# NinjaPCR-140720.net
KiCad netlist of a schematic drawn in EAGLE
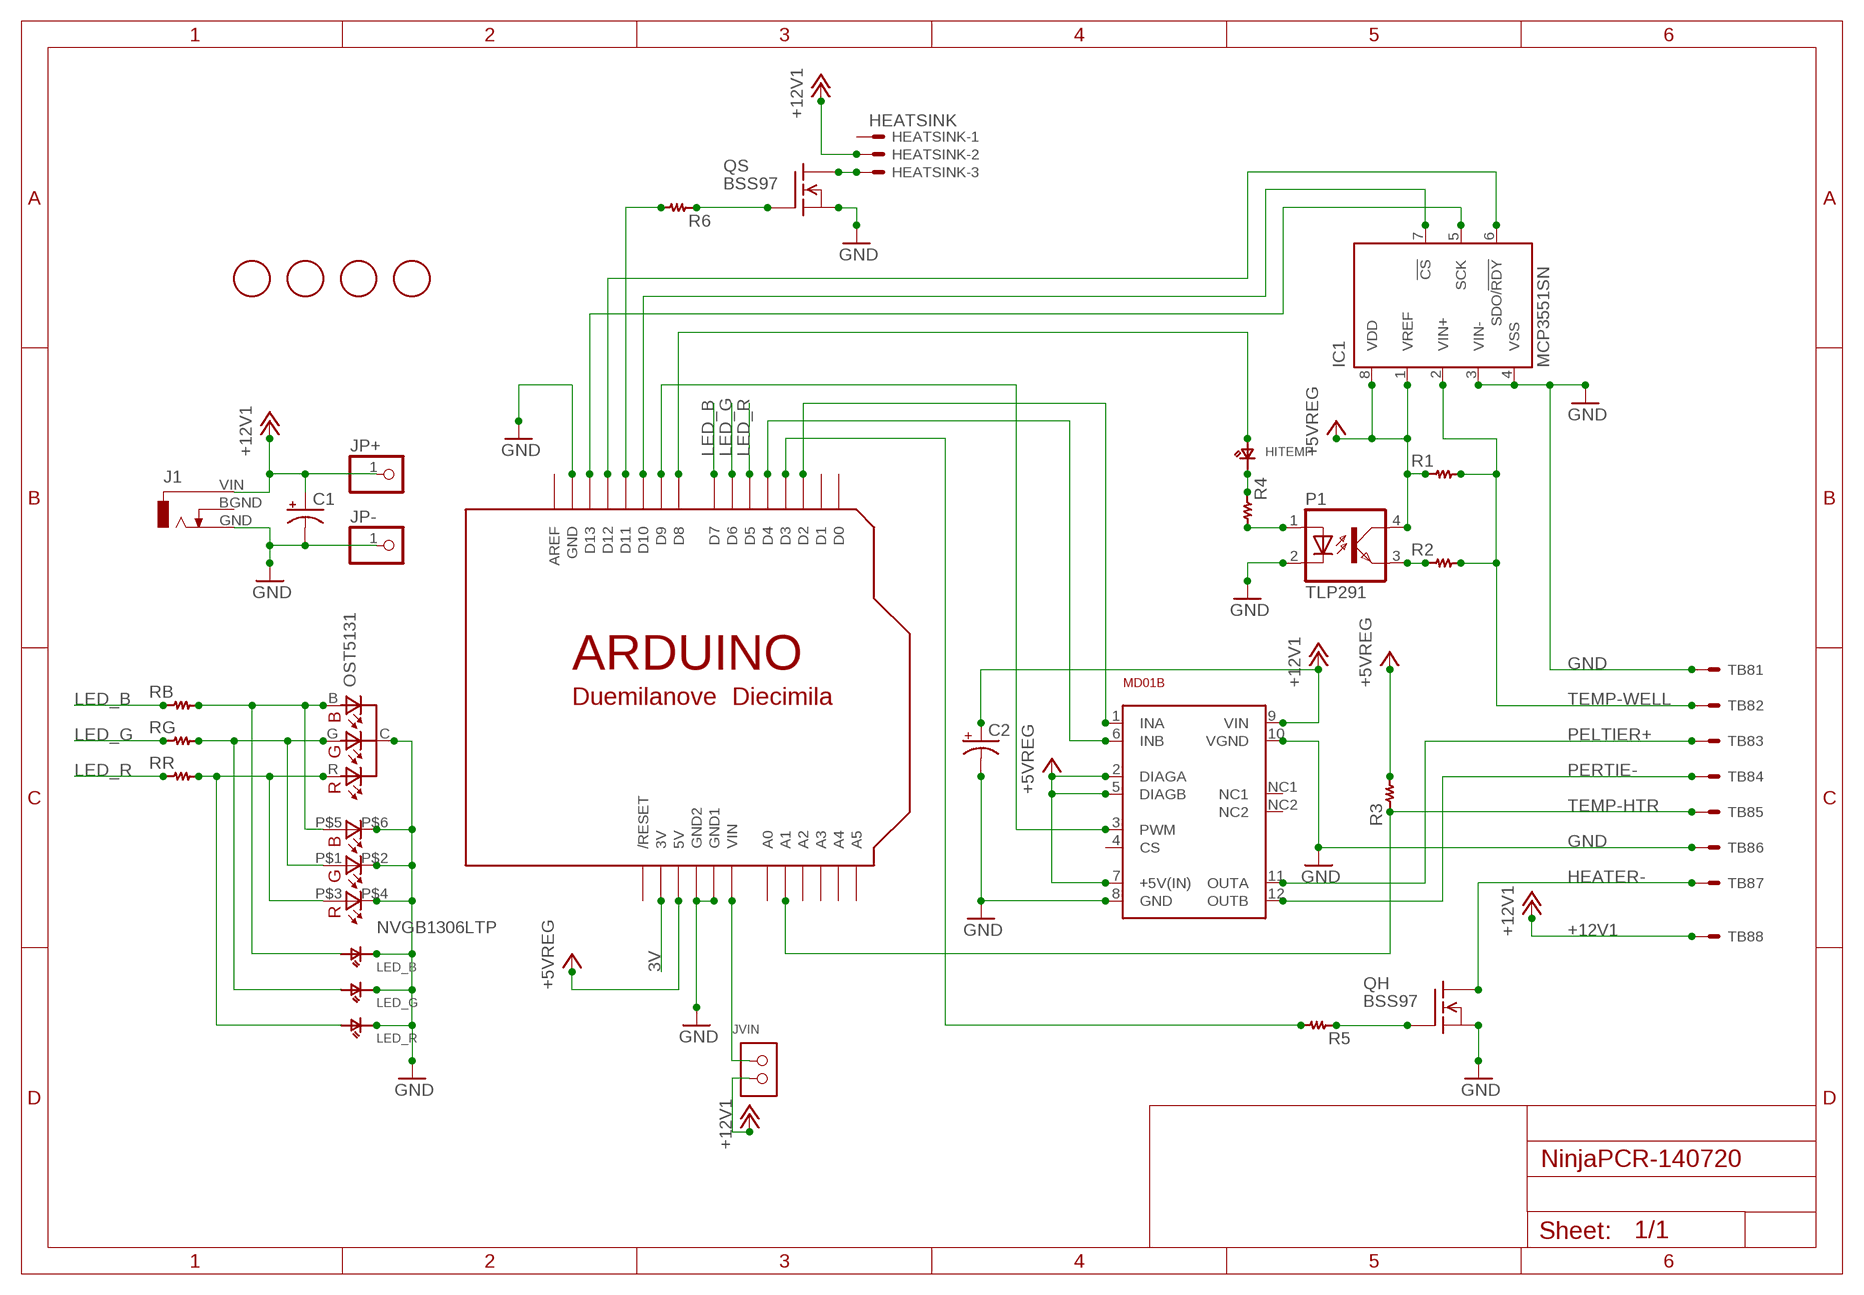
[diagram p0: schematic, sheet 1]

(export (version "E")
  (design (tool "Eeschema 10.0.6"))
  (components
    (comp (ref "C1")
      (value "CPOL-USE5-8.5")
      (footprint "eagle-import:E5-8,5")
      (libsource (lib "eagle-import") (part "CPOL-USE5-8.5"))
    )
    (comp (ref "C2")
      (value "CPOL-USE5-13")
      (footprint "eagle-import:E5-13")
      (libsource (lib "eagle-import") (part "CPOL-USE5-13"))
    )
    (comp (ref "HEATSINK")
      (value "HEATSINK")
      (footprint "eagle-import:22-23-2031")
      (fields (field (name "MF") "MOLEX") (field (name "MPN") "22-23-2031"))
      (libsource (lib "eagle-import") (part "22-23-2031"))
    )
    (comp (ref "HITEMP")
      (value "LED1608")
      (footprint "eagle-import:SMD_1608_0603")
      (libsource (lib "eagle-import") (part "LED1608"))
    )
    (comp (ref "IC1")
      (value "MCP3551SN")
      (footprint "eagle-import:SO-08")
      (fields (field (name "MPN") "MCP3551-E/SN"))
      (libsource (lib "eagle-import") (part "MCP355SN1"))
    )
    (comp (ref "J1")
      (value "DCJ0303")
      (footprint "eagle-import:DCJ0303")
      (libsource (lib "eagle-import") (part "DCJ0303"))
    )
    (comp (ref "JP+")
      (value "PINHD-1X1")
      (footprint "eagle-import:1X01")
      (libsource (lib "eagle-import") (part "PINHD-1X1"))
    )
    (comp (ref "JP-")
      (value "PINHD-1X1")
      (footprint "eagle-import:1X01")
      (libsource (lib "eagle-import") (part "PINHD-1X1"))
    )
    (comp (ref "JVIN")
      (value "1X02")
      (footprint "eagle-import:1X02_1.1_UNSIGNED")
      (libsource (lib "eagle-import") (part "1X02"))
    )
    (comp (ref "LED_B")
      (value "LED2012")
      (footprint "eagle-import:SMD_2012_0805")
      (libsource (lib "eagle-import") (part "LED2012"))
    )
    (comp (ref "LED_G")
      (value "LED2012")
      (footprint "eagle-import:SMD_2012_0805")
      (libsource (lib "eagle-import") (part "LED2012"))
    )
    (comp (ref "LED_R")
      (value "LED2012")
      (footprint "eagle-import:SMD_2012_0805")
      (libsource (lib "eagle-import") (part "LED2012"))
    )
    (comp (ref "MD01B")
      (value "VNH3SP30+4PINN")
      (footprint "eagle-import:VNH3SP30+4PIN_NOHOLES")
      (libsource (lib "eagle-import") (part "VNH3SP30+4PINN"))
    )
    (comp (ref "P1")
      (value "TLP291")
      (footprint "eagle-import:MINI-FLAT-4")
      (libsource (lib "eagle-import") (part "TLP283"))
    )
    (comp (ref "QH")
      (value "BSS97")
      (footprint "eagle-import:TO202")
      (libsource (lib "eagle-import") (part "BSS97"))
    )
    (comp (ref "QS")
      (value "BSS97")
      (footprint "eagle-import:TO202")
      (libsource (lib "eagle-import") (part "BSS97"))
    )
    (comp (ref "R1")
      (value "R_SMD1608")
      (footprint "eagle-import:SMD_1608_0603")
      (libsource (lib "eagle-import") (part "R_SMD1608"))
    )
    (comp (ref "R2")
      (value "R_SMD1608")
      (footprint "eagle-import:SMD_1608_0603")
      (libsource (lib "eagle-import") (part "R_SMD1608"))
    )
    (comp (ref "R3")
      (value "R_SMD1608")
      (footprint "eagle-import:SMD_1608_0603")
      (libsource (lib "eagle-import") (part "R_SMD1608"))
    )
    (comp (ref "R4")
      (value "R_SMD1608")
      (footprint "eagle-import:SMD_1608_0603")
      (libsource (lib "eagle-import") (part "R_SMD1608"))
    )
    (comp (ref "R5")
      (value "R_SMD1608")
      (footprint "eagle-import:SMD_1608_0603")
      (libsource (lib "eagle-import") (part "R_SMD1608"))
    )
    (comp (ref "R6")
      (value "R_SMD1608")
      (footprint "eagle-import:SMD_1608_0603")
      (libsource (lib "eagle-import") (part "R_SMD1608"))
    )
    (comp (ref "RB")
      (value "R_SMD1608")
      (footprint "eagle-import:SMD_1608_0603")
      (libsource (lib "eagle-import") (part "R_SMD1608"))
    )
    (comp (ref "RG")
      (value "R_SMD1608")
      (footprint "eagle-import:SMD_1608_0603")
      (libsource (lib "eagle-import") (part "R_SMD1608"))
    )
    (comp (ref "RR")
      (value "R_SMD1608")
      (footprint "eagle-import:SMD_1608_0603")
      (libsource (lib "eagle-import") (part "R_SMD1608"))
    )
    (comp (ref "TB8")
      (value "TB112A-2-8")
      (footprint "eagle-import:TB112A-2-8")
      (libsource (lib "eagle-import") (part "TB112A-2-8"))
    )
    (comp (ref "U$1")
      (value "OST5131")
      (footprint "eagle-import:OSTA5131")
      (libsource (lib "eagle-import") (part "OST5131"))
    )
    (comp (ref "U$2")
      (value "FIDUCIAL")
      (footprint "eagle-import:FIDUCIAL_1MM")
      (libsource (lib "eagle-import") (part "FIDUCIAL"))
    )
    (comp (ref "U$3")
      (value "ARDUINODUEMILANOVE")
      (footprint "eagle-import:ARDUINO")
      (libsource (lib "eagle-import") (part "ARDUINODUEMILANOVE"))
    )
    (comp (ref "U$4")
      (value "FIDUCIAL")
      (footprint "eagle-import:FIDUCIAL_1MM")
      (libsource (lib "eagle-import") (part "FIDUCIAL"))
    )
    (comp (ref "U$5")
      (value "FIDUCIAL")
      (footprint "eagle-import:FIDUCIAL_1MM")
      (libsource (lib "eagle-import") (part "FIDUCIAL"))
    )
    (comp (ref "U$6")
      (value "FIDUCIAL")
      (footprint "eagle-import:FIDUCIAL_1MM")
      (libsource (lib "eagle-import") (part "FIDUCIAL"))
    )
    (comp (ref "U$8")
      (value "NVGB1306LTP")
      (footprint "eagle-import:NVGB1306L_TINYPADS")
      (libsource (lib "eagle-import") (part "NVGB1306LTP"))
    )
  )
  (nets
    (net (code "1") (name "+5VREG") (class "Default")
      (node (ref "IC1") (pin "1") (pinfunction "VREF_1") (pintype "input"))
      (node (ref "IC1") (pin "8") (pinfunction "VDD_8") (pintype "power_in"))
      (node (ref "MD01B") (pin "2") (pinfunction "DIAGA_2") (pintype "passive"))
      (node (ref "MD01B") (pin "5") (pinfunction "DIAGB_5") (pintype "passive"))
      (node (ref "MD01B") (pin "7") (pinfunction "+5V(IN)_7") (pintype "power_in"))
      (node (ref "P1") (pin "4") (pinfunction "COL_4") (pintype "passive"))
      (node (ref "R1") (pin "P$1") (pinfunction "1_P$1") (pintype "bidirectional"))
      (node (ref "R3") (pin "P$2") (pinfunction "2_P$2") (pintype "bidirectional"))
      (node (ref "U$3") (pin "5V") (pinfunction "5V_5V") (pintype "power_in"))
    )
    (net (code "2") (name "+12V1") (class "Default")
      (node (ref "C1") (pin "+") (pinfunction "+_+") (pintype "passive"))
      (node (ref "C2") (pin "+") (pinfunction "+_+") (pintype "passive"))
      (node (ref "HEATSINK") (pin "2") (pinfunction "S_2") (pintype "passive"))
      (node (ref "J1") (pin "VIN") (pinfunction "VIN_VIN") (pintype "passive"))
      (node (ref "JP+") (pin "1") (pinfunction "1_1") (pintype "passive"))
      (node (ref "JVIN") (pin "2") (pinfunction "2_2") (pintype "passive"))
      (node (ref "MD01B") (pin "9") (pinfunction "VIN_9") (pintype "power_in"))
      (node (ref "TB8") (pin "P$8") (pinfunction "S_P$8") (pintype "passive"))
    )
    (net (code "3") (name "/3V") (class "Default")
      (node (ref "U$3") (pin "3V") (pinfunction "3V_3V") (pintype "power_in"))
    )
    (net (code "4") (name "/HEATER-") (class "Default")
      (node (ref "QH") (pin "2") (pinfunction "D_2") (pintype "passive"))
      (node (ref "TB8") (pin "P$7") (pinfunction "S_P$7") (pintype "passive"))
    )
    (net (code "5") (name "/LED_B") (class "Default")
      (node (ref "RB") (pin "P$1") (pinfunction "1_P$1") (pintype "bidirectional"))
      (node (ref "U$3") (pin "D7") (pinfunction "D7_D7") (pintype "bidirectional"))
    )
    (net (code "6") (name "/LED_G") (class "Default")
      (node (ref "RG") (pin "P$1") (pinfunction "1_P$1") (pintype "bidirectional"))
      (node (ref "U$3") (pin "D6") (pinfunction "D6_D6") (pintype "bidirectional"))
    )
    (net (code "7") (name "/LED_R") (class "Default")
      (node (ref "RR") (pin "P$1") (pinfunction "1_P$1") (pintype "bidirectional"))
      (node (ref "U$3") (pin "D5") (pinfunction "D5_D5") (pintype "bidirectional"))
    )
    (net (code "8") (name "/NC1") (class "Default")
      (node (ref "MD01B") (pin "NC1") (pinfunction "NC1_NC1") (pintype "power_in"))
    )
    (net (code "9") (name "/NC2") (class "Default")
      (node (ref "MD01B") (pin "NC2") (pinfunction "NC2_NC2") (pintype "power_in"))
    )
    (net (code "10") (name "/PELTIER+") (class "Default")
      (node (ref "MD01B") (pin "11") (pinfunction "OUTA_11") (pintype "passive"))
      (node (ref "TB8") (pin "P$3") (pinfunction "S_P$3") (pintype "passive"))
    )
    (net (code "11") (name "/PERTIE-") (class "Default")
      (node (ref "MD01B") (pin "12") (pinfunction "OUTB_12") (pintype "passive"))
      (node (ref "TB8") (pin "P$4") (pinfunction "S_P$4") (pintype "passive"))
    )
    (net (code "12") (name "/TEMP-HTR") (class "Default")
      (node (ref "R3") (pin "P$1") (pinfunction "1_P$1") (pintype "bidirectional"))
      (node (ref "TB8") (pin "P$5") (pinfunction "S_P$5") (pintype "passive"))
      (node (ref "U$3") (pin "A1") (pinfunction "A1_A1") (pintype "bidirectional"))
    )
    (net (code "13") (name "/TEMP-WELL") (class "Default")
      (node (ref "IC1") (pin "2") (pinfunction "VIN+_2") (pintype "input"))
      (node (ref "R1") (pin "P$2") (pinfunction "2_P$2") (pintype "bidirectional"))
      (node (ref "R2") (pin "P$2") (pinfunction "2_P$2") (pintype "bidirectional"))
      (node (ref "TB8") (pin "P$2") (pinfunction "S_P$2") (pintype "passive"))
    )
    (net (code "14") (name "GND") (class "Default")
      (node (ref "C1") (pin "-") (pinfunction "-_-") (pintype "passive"))
      (node (ref "C2") (pin "-") (pinfunction "-_-") (pintype "passive"))
      (node (ref "IC1") (pin "3") (pinfunction "VIN-_3") (pintype "input"))
      (node (ref "IC1") (pin "4") (pinfunction "VSS_4") (pintype "power_in"))
      (node (ref "J1") (pin "GND") (pinfunction "GND_GND") (pintype "passive"))
      (node (ref "JP-") (pin "1") (pinfunction "1_1") (pintype "passive"))
      (node (ref "LED_B") (pin "P$2") (pinfunction "C_P$2") (pintype "bidirectional"))
      (node (ref "LED_G") (pin "P$2") (pinfunction "C_P$2") (pintype "bidirectional"))
      (node (ref "LED_R") (pin "P$2") (pinfunction "C_P$2") (pintype "bidirectional"))
      (node (ref "MD01B") (pin "10") (pinfunction "VGND_10") (pintype "power_in"))
      (node (ref "MD01B") (pin "8") (pinfunction "GND_8") (pintype "power_in"))
      (node (ref "P1") (pin "2") (pinfunction "C_2") (pintype "passive"))
      (node (ref "QH") (pin "1") (pinfunction "S_1") (pintype "passive"))
      (node (ref "QS") (pin "1") (pinfunction "S_1") (pintype "passive"))
      (node (ref "TB8") (pin "P$1") (pinfunction "S_P$1") (pintype "passive"))
      (node (ref "TB8") (pin "P$6") (pinfunction "S_P$6") (pintype "passive"))
      (node (ref "U$1") (pin "C") (pinfunction "CC_C") (pintype "passive"))
      (node (ref "U$3") (pin "GND") (pinfunction "GND_GND") (pintype "power_in"))
      (node (ref "U$3") (pin "GND1") (pinfunction "GND1_GND1") (pintype "power_in"))
      (node (ref "U$3") (pin "GND2") (pinfunction "GND2_GND2") (pintype "power_in"))
      (node (ref "U$8") (pin "P$2") (pinfunction "GC_P$2") (pintype "passive"))
      (node (ref "U$8") (pin "P$4") (pinfunction "RC_P$4") (pintype "passive"))
      (node (ref "U$8") (pin "P$6") (pinfunction "BC_P$6") (pintype "passive"))
    )
    (net (code "15") (name "Net-(HEATSINKC-S)") (class "Default")
      (node (ref "HEATSINK") (pin "3") (pinfunction "S_3") (pintype "passive"))
      (node (ref "QS") (pin "2") (pinfunction "D_2") (pintype "passive"))
    )
    (net (code "16") (name "Net-(HITEMP-A)") (class "Default")
      (node (ref "HITEMP") (pin "P$1") (pinfunction "A_P$1") (pintype "bidirectional"))
      (node (ref "U$3") (pin "D8") (pinfunction "D8_D8") (pintype "bidirectional"))
    )
    (net (code "17") (name "Net-(HITEMP-C)") (class "Default")
      (node (ref "HITEMP") (pin "P$2") (pinfunction "C_P$2") (pintype "bidirectional"))
      (node (ref "R4") (pin "P$1") (pinfunction "1_P$1") (pintype "bidirectional"))
    )
    (net (code "18") (name "Net-(IC1-SCK)") (class "Default")
      (node (ref "IC1") (pin "5") (pinfunction "SCK_5") (pintype "input"))
      (node (ref "U$3") (pin "D13") (pinfunction "D13_D13") (pintype "bidirectional"))
    )
    (net (code "19") (name "Net-(IC1-SDO{slash}~{RDY})") (class "Default")
      (node (ref "IC1") (pin "6") (pinfunction "SDO/~{RDY}_6") (pintype "output"))
      (node (ref "U$3") (pin "D12") (pinfunction "D12_D12") (pintype "bidirectional"))
    )
    (net (code "20") (name "Net-(IC1-~{CS})") (class "Default")
      (node (ref "IC1") (pin "7") (pinfunction "~{CS}_7") (pintype "input"))
      (node (ref "U$3") (pin "D10") (pinfunction "D10_D10") (pintype "bidirectional"))
    )
    (net (code "21") (name "Net-(JVIN-Pad1)") (class "Default")
      (node (ref "JVIN") (pin "1") (pinfunction "1_1") (pintype "passive"))
      (node (ref "U$3") (pin "VIN") (pinfunction "VIN_VIN") (pintype "power_in"))
    )
    (net (code "22") (name "Net-(LED_B-A)") (class "Default")
      (node (ref "LED_B") (pin "P$1") (pinfunction "A_P$1") (pintype "bidirectional"))
      (node (ref "RB") (pin "P$2") (pinfunction "2_P$2") (pintype "bidirectional"))
      (node (ref "U$1") (pin "B") (pinfunction "BA_B") (pintype "passive"))
      (node (ref "U$8") (pin "P$5") (pinfunction "BA_P$5") (pintype "passive"))
    )
    (net (code "23") (name "Net-(LED_G-A)") (class "Default")
      (node (ref "LED_G") (pin "P$1") (pinfunction "A_P$1") (pintype "bidirectional"))
      (node (ref "RG") (pin "P$2") (pinfunction "2_P$2") (pintype "bidirectional"))
      (node (ref "U$1") (pin "G") (pinfunction "GA_G") (pintype "passive"))
      (node (ref "U$8") (pin "P$1") (pinfunction "GA_P$1") (pintype "passive"))
    )
    (net (code "24") (name "Net-(LED_R-A)") (class "Default")
      (node (ref "LED_R") (pin "P$1") (pinfunction "A_P$1") (pintype "bidirectional"))
      (node (ref "RR") (pin "P$2") (pinfunction "2_P$2") (pintype "bidirectional"))
      (node (ref "U$1") (pin "R") (pinfunction "RA_R") (pintype "passive"))
      (node (ref "U$8") (pin "P$3") (pinfunction "RA_P$3") (pintype "passive"))
    )
    (net (code "25") (name "Net-(MD01B-INA)") (class "Default")
      (node (ref "MD01B") (pin "1") (pinfunction "INA_1") (pintype "passive"))
      (node (ref "U$3") (pin "D2") (pinfunction "D2_D2") (pintype "bidirectional"))
    )
    (net (code "26") (name "Net-(MD01B-INB)") (class "Default")
      (node (ref "MD01B") (pin "6") (pinfunction "INB_6") (pintype "passive"))
      (node (ref "U$3") (pin "D4") (pinfunction "D4_D4") (pintype "bidirectional"))
    )
    (net (code "27") (name "Net-(MD01B-PWM)") (class "Default")
      (node (ref "MD01B") (pin "3") (pinfunction "PWM_3") (pintype "passive"))
      (node (ref "U$3") (pin "D9") (pinfunction "D9_D9") (pintype "bidirectional"))
    )
    (net (code "28") (name "Net-(P1-A)") (class "Default")
      (node (ref "P1") (pin "1") (pinfunction "A_1") (pintype "passive"))
      (node (ref "R4") (pin "P$2") (pinfunction "2_P$2") (pintype "bidirectional"))
    )
    (net (code "29") (name "Net-(P1-EMIT)") (class "Default")
      (node (ref "P1") (pin "3") (pinfunction "EMIT_3") (pintype "passive"))
      (node (ref "R2") (pin "P$1") (pinfunction "1_P$1") (pintype "bidirectional"))
    )
    (net (code "30") (name "Net-(QH-G)") (class "Default")
      (node (ref "QH") (pin "3") (pinfunction "G_3") (pintype "passive"))
      (node (ref "R5") (pin "P$1") (pinfunction "1_P$1") (pintype "bidirectional"))
    )
    (net (code "31") (name "Net-(QS-G)") (class "Default")
      (node (ref "QS") (pin "3") (pinfunction "G_3") (pintype "passive"))
      (node (ref "R6") (pin "P$1") (pinfunction "1_P$1") (pintype "bidirectional"))
    )
    (net (code "32") (name "Net-(R5-2)") (class "Default")
      (node (ref "R5") (pin "P$2") (pinfunction "2_P$2") (pintype "bidirectional"))
      (node (ref "U$3") (pin "D3") (pinfunction "D3_D3") (pintype "bidirectional"))
    )
    (net (code "33") (name "Net-(R6-2)") (class "Default")
      (node (ref "R6") (pin "P$2") (pinfunction "2_P$2") (pintype "bidirectional"))
      (node (ref "U$3") (pin "D11") (pinfunction "D11_D11") (pintype "bidirectional"))
    )
    (net (code "34") (name "unconnected-(HEATSINKA-S-Pad1)") (class "Default")
      (node (ref "HEATSINK") (pin "1") (pinfunction "S_1") (pintype "passive"))
    )
    (net (code "35") (name "unconnected-(J1-PadBGND)") (class "Default")
      (node (ref "J1") (pin "BGND") (pinfunction "BGND_BGND") (pintype "passive"))
    )
    (net (code "36") (name "unconnected-(MD01B-CS-Pad4)") (class "Default")
      (node (ref "MD01B") (pin "4") (pinfunction "CS_4") (pintype "passive"))
    )
    (net (code "37") (name "unconnected-(U$3-PadA0)") (class "Default")
      (node (ref "U$3") (pin "A0") (pinfunction "A0_A0") (pintype "bidirectional"))
    )
    (net (code "38") (name "unconnected-(U$3-PadA2)") (class "Default")
      (node (ref "U$3") (pin "A2") (pinfunction "A2_A2") (pintype "bidirectional"))
    )
    (net (code "39") (name "unconnected-(U$3-PadA3)") (class "Default")
      (node (ref "U$3") (pin "A3") (pinfunction "A3_A3") (pintype "bidirectional"))
    )
    (net (code "40") (name "unconnected-(U$3-PadA4)") (class "Default")
      (node (ref "U$3") (pin "A4") (pinfunction "A4_A4") (pintype "bidirectional"))
    )
    (net (code "41") (name "unconnected-(U$3-PadA5)") (class "Default")
      (node (ref "U$3") (pin "A5") (pinfunction "A5_A5") (pintype "bidirectional"))
    )
    (net (code "42") (name "unconnected-(U$3-PadAREF)") (class "Default")
      (node (ref "U$3") (pin "AREF") (pinfunction "AREF_AREF") (pintype "bidirectional"))
    )
    (net (code "43") (name "unconnected-(U$3-PadD0)") (class "Default")
      (node (ref "U$3") (pin "D0") (pinfunction "D0_D0") (pintype "bidirectional"))
    )
    (net (code "44") (name "unconnected-(U$3-PadD1)") (class "Default")
      (node (ref "U$3") (pin "D1") (pinfunction "D1_D1") (pintype "bidirectional"))
    )
    (net (code "45") (name "unconnected-(U$3-{slash}RESET-PadRESET)") (class "Default")
      (node (ref "U$3") (pin "RESET") (pinfunction "/RESET_RESET") (pintype "bidirectional"))
    )
  )
)
